# Control.net
KiCad netlist of a schematic drawn in Altium Designer
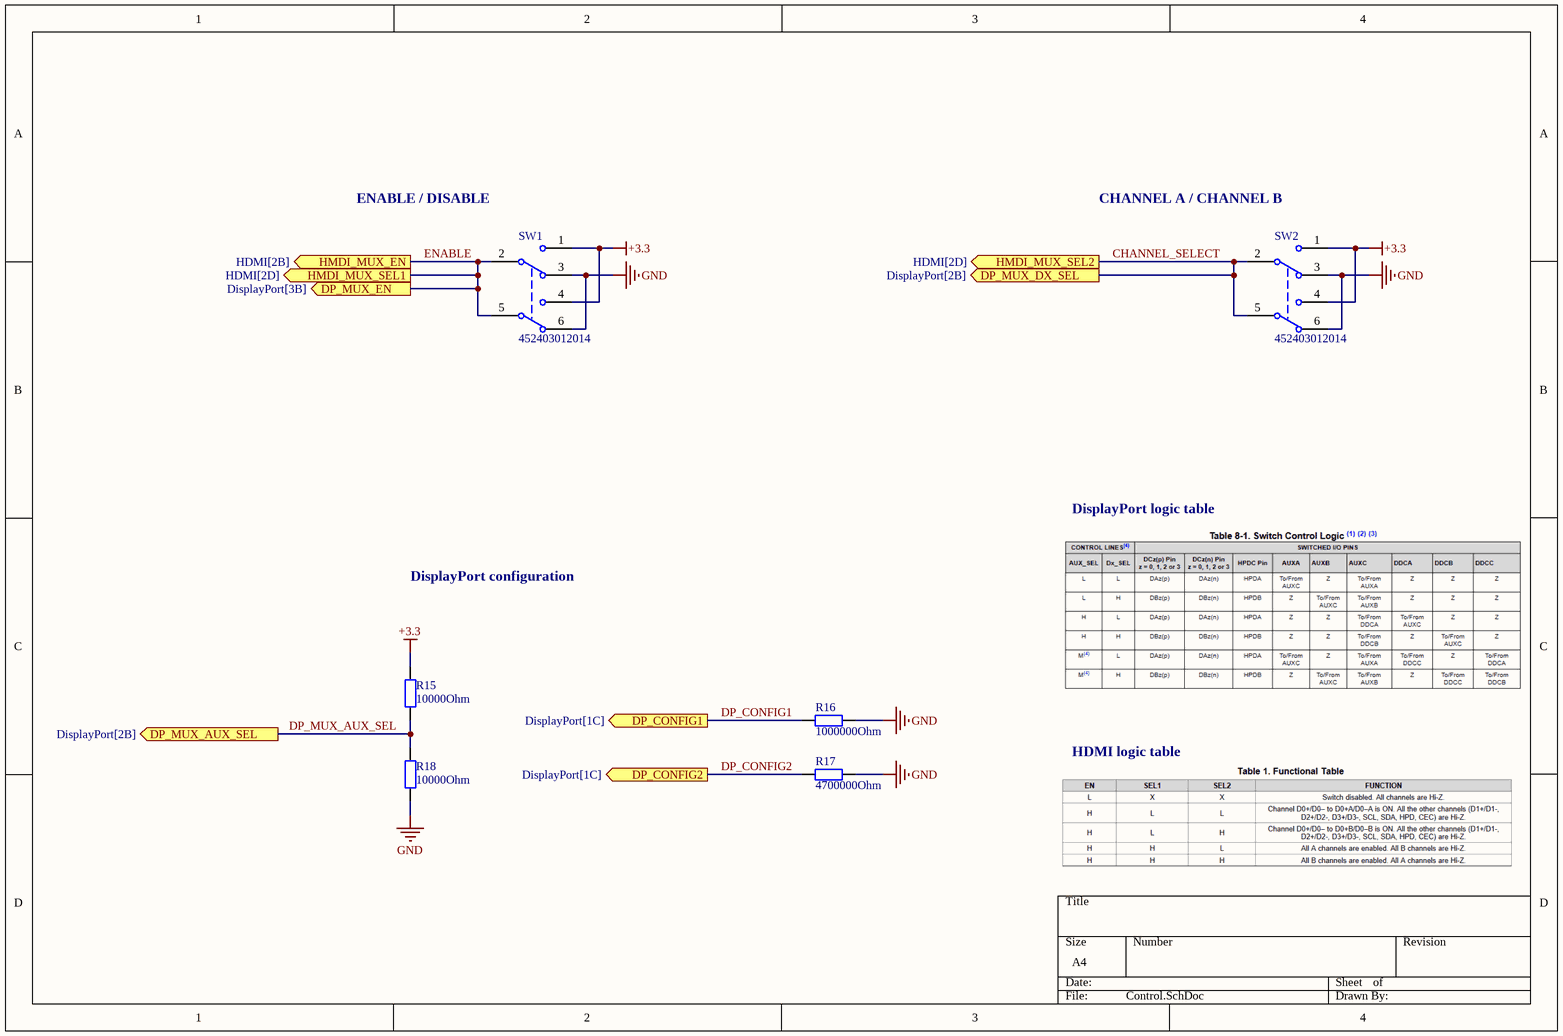
[diagram p0: Control.SchDoc]

(export (version "E")
  (design (tool "Eeschema 10.0.6"))
  (components
    (comp (ref "R15")
      (value "10000Ohm, 100mW")
      (footprint "WRIS-RSKS_0402")
      (description "WRIS-RSKS Thick Film Resistor, size 0402, 10000Ohm, 100mW")
      (fields
        (field (name "MANUFACTURER PART NUMBER") "560112110020")
        (field (name "MANUFACTURER") "Wurth Elektronik")
        (field (name "RESISTANCE") "10000Ohm")
      )
      (libsource (lib "WRIS-RSKS") (part "560112110020"))
    )
    (comp (ref "R16")
      (value "1000000Ohm, 100mW")
      (footprint "WRIS-RSKS_0402")
      (description "WRIS-RSKS Thick Film Resistor, size 0402, 1000000Ohm, 100mW")
      (fields
        (field (name "MANUFACTURER PART NUMBER") "560112110033")
        (field (name "MANUFACTURER") "Wurth Elektronik")
        (field (name "RESISTANCE") "1000000Ohm")
      )
      (libsource (lib "WRIS-RSKS") (part "560112110033"))
    )
    (comp (ref "R17")
      (value "4700000Ohm, 250mW")
      (footprint "WRIS-RSKS_1206_Reflow")
      (description "WRIS-RSKS Thick Film Resistor, size 1206, 4700000Ohm, 250mW")
      (fields
        (field (name "MANUFACTURER PART NUMBER") "560112132029")
        (field (name "MANUFACTURER") "Wurth Elektronik")
        (field (name "RESISTANCE") "4700000Ohm")
      )
      (libsource (lib "WRIS-RSKS") (part "560112132029"))
    )
    (comp (ref "R18")
      (value "10000Ohm, 100mW")
      (footprint "WRIS-RSKS_0402")
      (description "WRIS-RSKS Thick Film Resistor, size 0402, 10000Ohm, 100mW")
      (fields
        (field (name "MANUFACTURER PART NUMBER") "560112110020")
        (field (name "MANUFACTURER") "Wurth Elektronik")
        (field (name "RESISTANCE") "10000Ohm")
      )
      (libsource (lib "WRIS-RSKS") (part "560112110020"))
    )
    (comp (ref "SW1")
      (value "452403012014")
      (footprint "452403012014")
      (description "452403012014 Slide Switch, Dpdt, 0.3A, 6Vdc, Smd Rohs Compliant: Yes")
      (libsource (lib "Altium Content Vault") (part "DPDT_WS-SLSV"))
    )
    (comp (ref "SW2")
      (value "452403012014")
      (footprint "452403012014")
      (description "452403012014 Slide Switch, Dpdt, 0.3A, 6Vdc, Smd Rohs Compliant: Yes")
      (libsource (lib "Altium Content Vault") (part "DPDT_WS-SLSV"))
    )
  )
  (nets
    (net (code "1") (name "+3.3") (class "Default")
      (node (ref "R15") (pin "2") (pinfunction "2_2") (pintype "passive"))
      (node (ref "SW1") (pin "1") (pinfunction "1_1") (pintype "passive"))
      (node (ref "SW1") (pin "4") (pinfunction "4_4") (pintype "passive"))
      (node (ref "SW2") (pin "1") (pinfunction "1_1") (pintype "passive"))
      (node (ref "SW2") (pin "4") (pinfunction "4_4") (pintype "passive"))
    )
    (net (code "2") (name "/CHANNEL_SELECT") (class "Default")
      (node (ref "SW2") (pin "2") (pinfunction "COM_2") (pintype "passive"))
      (node (ref "SW2") (pin "5") (pinfunction "COM_5") (pintype "passive"))
    )
    (net (code "3") (name "/DP_CONFIG1") (class "Default")
      (node (ref "R16") (pin "2") (pinfunction "2_2") (pintype "passive"))
    )
    (net (code "4") (name "/DP_CONFIG2") (class "Default")
      (node (ref "R17") (pin "2") (pinfunction "2_2") (pintype "passive"))
    )
    (net (code "5") (name "/DP_MUX_AUX_SEL") (class "Default")
      (node (ref "R15") (pin "1") (pinfunction "1_1") (pintype "passive"))
      (node (ref "R18") (pin "2") (pinfunction "2_2") (pintype "passive"))
    )
    (net (code "6") (name "/ENABLE") (class "Default")
      (node (ref "SW1") (pin "2") (pinfunction "COM_2") (pintype "passive"))
      (node (ref "SW1") (pin "5") (pinfunction "COM_5") (pintype "passive"))
    )
    (net (code "7") (name "GND") (class "Default")
      (node (ref "R16") (pin "1") (pinfunction "1_1") (pintype "passive"))
      (node (ref "R17") (pin "1") (pinfunction "1_1") (pintype "passive"))
      (node (ref "R18") (pin "1") (pinfunction "1_1") (pintype "passive"))
      (node (ref "SW1") (pin "3") (pinfunction "3_3") (pintype "passive"))
      (node (ref "SW1") (pin "6") (pinfunction "6_6") (pintype "passive"))
      (node (ref "SW2") (pin "3") (pinfunction "3_3") (pintype "passive"))
      (node (ref "SW2") (pin "6") (pinfunction "6_6") (pintype "passive"))
    )
  )
)
